# oled.net
KiCad netlist of a schematic drawn in EAGLE
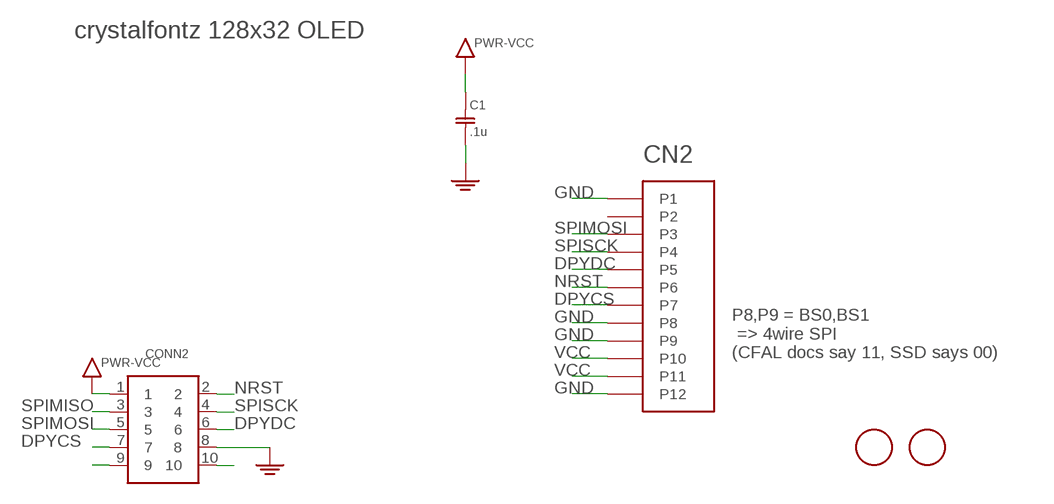
[diagram p0: schematic, sheet 1]

(export (version "E")
  (design (tool "Eeschema 10.0.6"))
  (components
    (comp (ref "C1")
      (value ".1u")
      (footprint "eagle-import:SMD0603")
      (libsource (lib "eagle-import") (part "C0603"))
    )
    (comp (ref "CN2")
      (value "MA12-1")
      (footprint "eagle-import:M05-1X12-RA")
      (libsource (lib "eagle-import") (part "MA12-1"))
    )
    (comp (ref "CONN2")
      (value "HEADER-5X2-PTH")
      (footprint "eagle-import:HEADER-5X2-PTH")
      (libsource (lib "eagle-import") (part "HEADER-5X2-PTH"))
    )
    (comp (ref "U$1")
      (value "FIDUCIAL")
      (footprint "eagle-import:FIDUCIAL_1MM")
      (libsource (lib "eagle-import") (part "FIDUCIAL"))
    )
    (comp (ref "U$2")
      (value "FIDUCIAL")
      (footprint "eagle-import:FIDUCIAL_1MM")
      (libsource (lib "eagle-import") (part "FIDUCIAL"))
    )
  )
  (nets
    (net (code "1") (name "/DPYCS") (class "Default")
      (node (ref "CN2") (pin "P7") (pinfunction "P7_P7") (pintype "bidirectional"))
      (node (ref "CONN2") (pin "7") (pinfunction "7_7") (pintype "passive"))
    )
    (net (code "2") (name "/DPYDC") (class "Default")
      (node (ref "CN2") (pin "P5") (pinfunction "P5_P5") (pintype "bidirectional"))
      (node (ref "CONN2") (pin "6") (pinfunction "6_6") (pintype "passive"))
    )
    (net (code "3") (name "/NRST") (class "Default")
      (node (ref "CN2") (pin "P6") (pinfunction "P6_P6") (pintype "bidirectional"))
      (node (ref "CONN2") (pin "2") (pinfunction "2_2") (pintype "passive"))
    )
    (net (code "4") (name "/SPIMISO") (class "Default")
      (node (ref "CONN2") (pin "3") (pinfunction "3_3") (pintype "passive"))
    )
    (net (code "5") (name "/SPIMOSI") (class "Default")
      (node (ref "CN2") (pin "P3") (pinfunction "P3_P3") (pintype "bidirectional"))
      (node (ref "CONN2") (pin "5") (pinfunction "5_5") (pintype "passive"))
    )
    (net (code "6") (name "/SPISCK") (class "Default")
      (node (ref "CN2") (pin "P4") (pinfunction "P4_P4") (pintype "bidirectional"))
      (node (ref "CONN2") (pin "4") (pinfunction "4_4") (pintype "passive"))
    )
    (net (code "7") (name "PWR-GND") (class "Default")
      (node (ref "C1") (pin "2") (pinfunction "P$2_2") (pintype "passive"))
      (node (ref "CN2") (pin "P1") (pinfunction "P1_P1") (pintype "bidirectional"))
      (node (ref "CN2") (pin "P12") (pinfunction "P12_P12") (pintype "bidirectional"))
      (node (ref "CN2") (pin "P8") (pinfunction "P8_P8") (pintype "bidirectional"))
      (node (ref "CN2") (pin "P9") (pinfunction "P9_P9") (pintype "bidirectional"))
      (node (ref "CONN2") (pin "8") (pinfunction "8_8") (pintype "passive"))
    )
    (net (code "8") (name "PWR-VCC") (class "Default")
      (node (ref "C1") (pin "1") (pinfunction "P$1_1") (pintype "passive"))
      (node (ref "CN2") (pin "P10") (pinfunction "P10_P10") (pintype "bidirectional"))
      (node (ref "CN2") (pin "P11") (pinfunction "P11_P11") (pintype "bidirectional"))
      (node (ref "CONN2") (pin "1") (pinfunction "1_1") (pintype "passive"))
    )
    (net (code "9") (name "unconnected-(CN2-PadP2)") (class "Default")
      (node (ref "CN2") (pin "P2") (pinfunction "P2_P2") (pintype "bidirectional"))
    )
    (net (code "10") (name "unconnected-(CONN2-Pad9)") (class "Default")
      (node (ref "CONN2") (pin "9") (pinfunction "9_9") (pintype "passive"))
    )
    (net (code "11") (name "unconnected-(CONN2-Pad10)") (class "Default")
      (node (ref "CONN2") (pin "10") (pinfunction "10_10") (pintype "passive"))
    )
  )
)
